# AD_inputs.net
KiCad netlist of a schematic drawn in EAGLE
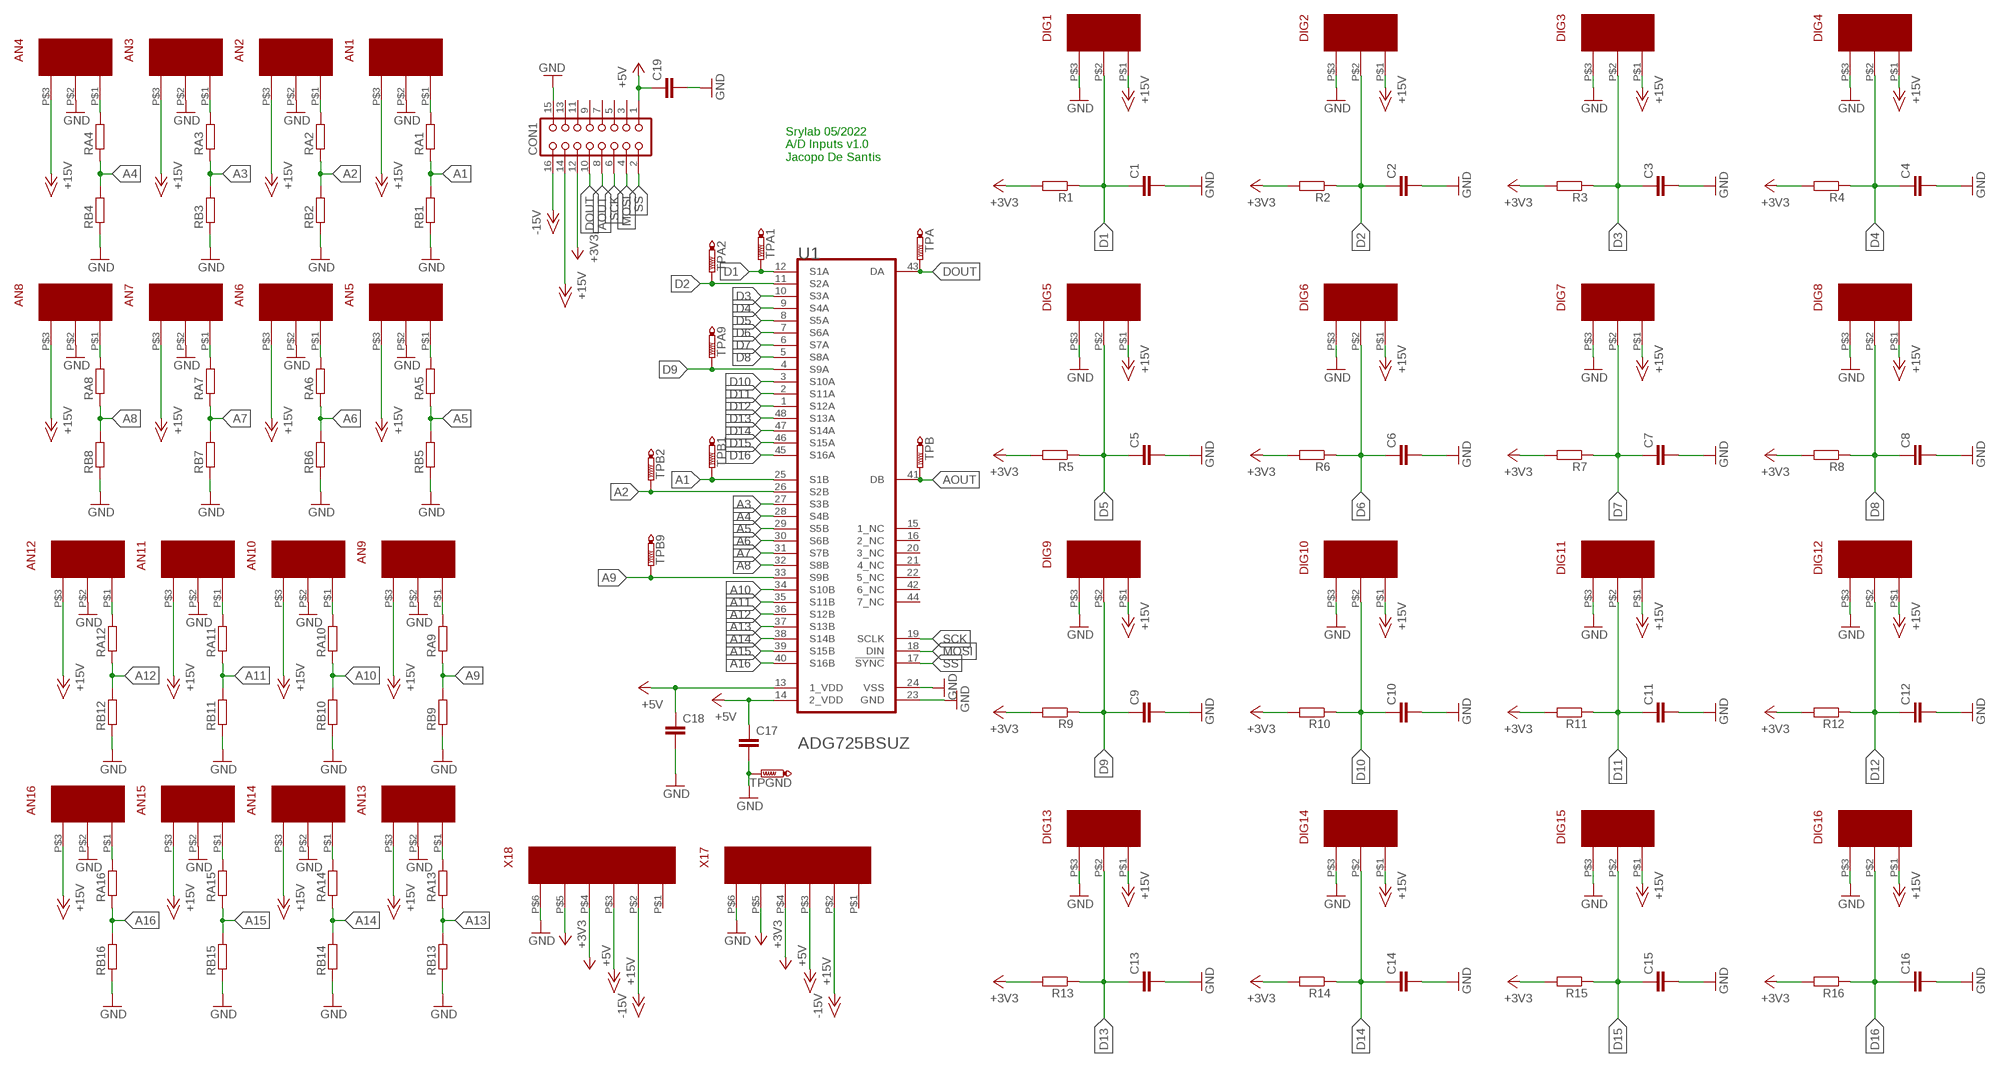
[diagram p0: schematic, sheet 1]

(export (version "E")
  (design (tool "Eeschema 10.0.6"))
  (components
    (comp (ref "AN1")
      (value "3PIN_CON")
      (footprint "eagle-import:3PIN_CON")
      (libsource (lib "eagle-import") (part "3PIN_CON"))
    )
    (comp (ref "AN2")
      (value "3PIN_CON")
      (footprint "eagle-import:3PIN_CON")
      (libsource (lib "eagle-import") (part "3PIN_CON"))
    )
    (comp (ref "AN3")
      (value "3PIN_CON")
      (footprint "eagle-import:3PIN_CON")
      (libsource (lib "eagle-import") (part "3PIN_CON"))
    )
    (comp (ref "AN4")
      (value "3PIN_CON")
      (footprint "eagle-import:3PIN_CON")
      (libsource (lib "eagle-import") (part "3PIN_CON"))
    )
    (comp (ref "AN5")
      (value "3PIN_CON")
      (footprint "eagle-import:3PIN_CON")
      (libsource (lib "eagle-import") (part "3PIN_CON"))
    )
    (comp (ref "AN6")
      (value "3PIN_CON")
      (footprint "eagle-import:3PIN_CON")
      (libsource (lib "eagle-import") (part "3PIN_CON"))
    )
    (comp (ref "AN7")
      (value "3PIN_CON")
      (footprint "eagle-import:3PIN_CON")
      (libsource (lib "eagle-import") (part "3PIN_CON"))
    )
    (comp (ref "AN8")
      (value "3PIN_CON")
      (footprint "eagle-import:3PIN_CON")
      (libsource (lib "eagle-import") (part "3PIN_CON"))
    )
    (comp (ref "AN9")
      (value "3PIN_CON")
      (footprint "eagle-import:3PIN_CON")
      (libsource (lib "eagle-import") (part "3PIN_CON"))
    )
    (comp (ref "AN10")
      (value "3PIN_CON")
      (footprint "eagle-import:3PIN_CON")
      (libsource (lib "eagle-import") (part "3PIN_CON"))
    )
    (comp (ref "AN11")
      (value "3PIN_CON")
      (footprint "eagle-import:3PIN_CON")
      (libsource (lib "eagle-import") (part "3PIN_CON"))
    )
    (comp (ref "AN12")
      (value "3PIN_CON")
      (footprint "eagle-import:3PIN_CON")
      (libsource (lib "eagle-import") (part "3PIN_CON"))
    )
    (comp (ref "AN13")
      (value "3PIN_CON")
      (footprint "eagle-import:3PIN_CON")
      (libsource (lib "eagle-import") (part "3PIN_CON"))
    )
    (comp (ref "AN14")
      (value "3PIN_CON")
      (footprint "eagle-import:3PIN_CON")
      (libsource (lib "eagle-import") (part "3PIN_CON"))
    )
    (comp (ref "AN15")
      (value "3PIN_CON")
      (footprint "eagle-import:3PIN_CON")
      (libsource (lib "eagle-import") (part "3PIN_CON"))
    )
    (comp (ref "AN16")
      (value "3PIN_CON")
      (footprint "eagle-import:3PIN_CON")
      (libsource (lib "eagle-import") (part "3PIN_CON"))
    )
    (comp (ref "C1")
      (value "C-EU_SMD0805")
      (footprint "eagle-import:C0805")
      (libsource (lib "eagle-import") (part "C-EU_SMD0805"))
    )
    (comp (ref "C2")
      (value "C-EU_SMD0805")
      (footprint "eagle-import:C0805")
      (libsource (lib "eagle-import") (part "C-EU_SMD0805"))
    )
    (comp (ref "C3")
      (value "C-EU_SMD0805")
      (footprint "eagle-import:C0805")
      (libsource (lib "eagle-import") (part "C-EU_SMD0805"))
    )
    (comp (ref "C4")
      (value "C-EU_SMD0805")
      (footprint "eagle-import:C0805")
      (libsource (lib "eagle-import") (part "C-EU_SMD0805"))
    )
    (comp (ref "C5")
      (value "C-EU_SMD0805")
      (footprint "eagle-import:C0805")
      (libsource (lib "eagle-import") (part "C-EU_SMD0805"))
    )
    (comp (ref "C6")
      (value "C-EU_SMD0805")
      (footprint "eagle-import:C0805")
      (libsource (lib "eagle-import") (part "C-EU_SMD0805"))
    )
    (comp (ref "C7")
      (value "C-EU_SMD0805")
      (footprint "eagle-import:C0805")
      (libsource (lib "eagle-import") (part "C-EU_SMD0805"))
    )
    (comp (ref "C8")
      (value "C-EU_SMD0805")
      (footprint "eagle-import:C0805")
      (libsource (lib "eagle-import") (part "C-EU_SMD0805"))
    )
    (comp (ref "C9")
      (value "C-EU_SMD0805")
      (footprint "eagle-import:C0805")
      (libsource (lib "eagle-import") (part "C-EU_SMD0805"))
    )
    (comp (ref "C10")
      (value "C-EU_SMD0805")
      (footprint "eagle-import:C0805")
      (libsource (lib "eagle-import") (part "C-EU_SMD0805"))
    )
    (comp (ref "C11")
      (value "C-EU_SMD0805")
      (footprint "eagle-import:C0805")
      (libsource (lib "eagle-import") (part "C-EU_SMD0805"))
    )
    (comp (ref "C12")
      (value "C-EU_SMD0805")
      (footprint "eagle-import:C0805")
      (libsource (lib "eagle-import") (part "C-EU_SMD0805"))
    )
    (comp (ref "C13")
      (value "C-EU_SMD0805")
      (footprint "eagle-import:C0805")
      (libsource (lib "eagle-import") (part "C-EU_SMD0805"))
    )
    (comp (ref "C14")
      (value "C-EU_SMD0805")
      (footprint "eagle-import:C0805")
      (libsource (lib "eagle-import") (part "C-EU_SMD0805"))
    )
    (comp (ref "C15")
      (value "C-EU_SMD0805")
      (footprint "eagle-import:C0805")
      (libsource (lib "eagle-import") (part "C-EU_SMD0805"))
    )
    (comp (ref "C16")
      (value "C-EU_SMD0805")
      (footprint "eagle-import:C0805")
      (libsource (lib "eagle-import") (part "C-EU_SMD0805"))
    )
    (comp (ref "C17")
      (value "C-EU_SMDC1206H/D")
      (footprint "eagle-import:C1206H_D")
      (libsource (lib "eagle-import") (part "C-EU_SMDC1206H/D"))
    )
    (comp (ref "C18")
      (value "C-EU_SMDC1206H/D")
      (footprint "eagle-import:C1206H_D")
      (libsource (lib "eagle-import") (part "C-EU_SMDC1206H/D"))
    )
    (comp (ref "C19")
      (value "C-EU_SMDC1206H/D")
      (footprint "eagle-import:C1206H_D")
      (libsource (lib "eagle-import") (part "C-EU_SMDC1206H/D"))
    )
    (comp (ref "CON1")
      (value "CON16L")
      (footprint "eagle-import:CON16L")
      (libsource (lib "eagle-import") (part "CON16L"))
    )
    (comp (ref "DIG1")
      (value "3PIN_CON")
      (footprint "eagle-import:3PIN_CON")
      (libsource (lib "eagle-import") (part "3PIN_CON"))
    )
    (comp (ref "DIG2")
      (value "3PIN_CON")
      (footprint "eagle-import:3PIN_CON")
      (libsource (lib "eagle-import") (part "3PIN_CON"))
    )
    (comp (ref "DIG3")
      (value "3PIN_CON")
      (footprint "eagle-import:3PIN_CON")
      (libsource (lib "eagle-import") (part "3PIN_CON"))
    )
    (comp (ref "DIG4")
      (value "3PIN_CON")
      (footprint "eagle-import:3PIN_CON")
      (libsource (lib "eagle-import") (part "3PIN_CON"))
    )
    (comp (ref "DIG5")
      (value "3PIN_CON")
      (footprint "eagle-import:3PIN_CON")
      (libsource (lib "eagle-import") (part "3PIN_CON"))
    )
    (comp (ref "DIG6")
      (value "3PIN_CON")
      (footprint "eagle-import:3PIN_CON")
      (libsource (lib "eagle-import") (part "3PIN_CON"))
    )
    (comp (ref "DIG7")
      (value "3PIN_CON")
      (footprint "eagle-import:3PIN_CON")
      (libsource (lib "eagle-import") (part "3PIN_CON"))
    )
    (comp (ref "DIG8")
      (value "3PIN_CON")
      (footprint "eagle-import:3PIN_CON")
      (libsource (lib "eagle-import") (part "3PIN_CON"))
    )
    (comp (ref "DIG9")
      (value "3PIN_CON")
      (footprint "eagle-import:3PIN_CON")
      (libsource (lib "eagle-import") (part "3PIN_CON"))
    )
    (comp (ref "DIG10")
      (value "3PIN_CON")
      (footprint "eagle-import:3PIN_CON")
      (libsource (lib "eagle-import") (part "3PIN_CON"))
    )
    (comp (ref "DIG11")
      (value "3PIN_CON")
      (footprint "eagle-import:3PIN_CON")
      (libsource (lib "eagle-import") (part "3PIN_CON"))
    )
    (comp (ref "DIG12")
      (value "3PIN_CON")
      (footprint "eagle-import:3PIN_CON")
      (libsource (lib "eagle-import") (part "3PIN_CON"))
    )
    (comp (ref "DIG13")
      (value "3PIN_CON")
      (footprint "eagle-import:3PIN_CON")
      (libsource (lib "eagle-import") (part "3PIN_CON"))
    )
    (comp (ref "DIG14")
      (value "3PIN_CON")
      (footprint "eagle-import:3PIN_CON")
      (libsource (lib "eagle-import") (part "3PIN_CON"))
    )
    (comp (ref "DIG15")
      (value "3PIN_CON")
      (footprint "eagle-import:3PIN_CON")
      (libsource (lib "eagle-import") (part "3PIN_CON"))
    )
    (comp (ref "DIG16")
      (value "3PIN_CON")
      (footprint "eagle-import:3PIN_CON")
      (libsource (lib "eagle-import") (part "3PIN_CON"))
    )
    (comp (ref "R1")
      (value "R-EU_SMD0805H")
      (footprint "eagle-import:R0805H")
      (libsource (lib "eagle-import") (part "R-EU_SMD0805H"))
    )
    (comp (ref "R2")
      (value "R-EU_SMD0805H")
      (footprint "eagle-import:R0805H")
      (libsource (lib "eagle-import") (part "R-EU_SMD0805H"))
    )
    (comp (ref "R3")
      (value "R-EU_SMD0805H")
      (footprint "eagle-import:R0805H")
      (libsource (lib "eagle-import") (part "R-EU_SMD0805H"))
    )
    (comp (ref "R4")
      (value "R-EU_SMD0805H")
      (footprint "eagle-import:R0805H")
      (libsource (lib "eagle-import") (part "R-EU_SMD0805H"))
    )
    (comp (ref "R5")
      (value "R-EU_SMD0805H")
      (footprint "eagle-import:R0805H")
      (libsource (lib "eagle-import") (part "R-EU_SMD0805H"))
    )
    (comp (ref "R6")
      (value "R-EU_SMD0805H")
      (footprint "eagle-import:R0805H")
      (libsource (lib "eagle-import") (part "R-EU_SMD0805H"))
    )
    (comp (ref "R7")
      (value "R-EU_SMD0805H")
      (footprint "eagle-import:R0805H")
      (libsource (lib "eagle-import") (part "R-EU_SMD0805H"))
    )
    (comp (ref "R8")
      (value "R-EU_SMD0805H")
      (footprint "eagle-import:R0805H")
      (libsource (lib "eagle-import") (part "R-EU_SMD0805H"))
    )
    (comp (ref "R9")
      (value "R-EU_SMD0805H")
      (footprint "eagle-import:R0805H")
      (libsource (lib "eagle-import") (part "R-EU_SMD0805H"))
    )
    (comp (ref "R10")
      (value "R-EU_SMD0805H")
      (footprint "eagle-import:R0805H")
      (libsource (lib "eagle-import") (part "R-EU_SMD0805H"))
    )
    (comp (ref "R11")
      (value "R-EU_SMD0805H")
      (footprint "eagle-import:R0805H")
      (libsource (lib "eagle-import") (part "R-EU_SMD0805H"))
    )
    (comp (ref "R12")
      (value "R-EU_SMD0805H")
      (footprint "eagle-import:R0805H")
      (libsource (lib "eagle-import") (part "R-EU_SMD0805H"))
    )
    (comp (ref "R13")
      (value "R-EU_SMD0805H")
      (footprint "eagle-import:R0805H")
      (libsource (lib "eagle-import") (part "R-EU_SMD0805H"))
    )
    (comp (ref "R14")
      (value "R-EU_SMD0805H")
      (footprint "eagle-import:R0805H")
      (libsource (lib "eagle-import") (part "R-EU_SMD0805H"))
    )
    (comp (ref "R15")
      (value "R-EU_SMD0805H")
      (footprint "eagle-import:R0805H")
      (libsource (lib "eagle-import") (part "R-EU_SMD0805H"))
    )
    (comp (ref "R16")
      (value "R-EU_SMD0805H")
      (footprint "eagle-import:R0805H")
      (libsource (lib "eagle-import") (part "R-EU_SMD0805H"))
    )
    (comp (ref "RA1")
      (value "R-EU_SMD0805H")
      (footprint "eagle-import:R0805H")
      (libsource (lib "eagle-import") (part "R-EU_SMD0805H"))
    )
    (comp (ref "RA2")
      (value "R-EU_SMD0805H")
      (footprint "eagle-import:R0805H")
      (libsource (lib "eagle-import") (part "R-EU_SMD0805H"))
    )
    (comp (ref "RA3")
      (value "R-EU_SMD0805H")
      (footprint "eagle-import:R0805H")
      (libsource (lib "eagle-import") (part "R-EU_SMD0805H"))
    )
    (comp (ref "RA4")
      (value "R-EU_SMD0805H")
      (footprint "eagle-import:R0805H")
      (libsource (lib "eagle-import") (part "R-EU_SMD0805H"))
    )
    (comp (ref "RA5")
      (value "R-EU_SMD0805H")
      (footprint "eagle-import:R0805H")
      (libsource (lib "eagle-import") (part "R-EU_SMD0805H"))
    )
    (comp (ref "RA6")
      (value "R-EU_SMD0805H")
      (footprint "eagle-import:R0805H")
      (libsource (lib "eagle-import") (part "R-EU_SMD0805H"))
    )
    (comp (ref "RA7")
      (value "R-EU_SMD0805H")
      (footprint "eagle-import:R0805H")
      (libsource (lib "eagle-import") (part "R-EU_SMD0805H"))
    )
    (comp (ref "RA8")
      (value "R-EU_SMD0805H")
      (footprint "eagle-import:R0805H")
      (libsource (lib "eagle-import") (part "R-EU_SMD0805H"))
    )
    (comp (ref "RA9")
      (value "R-EU_SMD0805H")
      (footprint "eagle-import:R0805H")
      (libsource (lib "eagle-import") (part "R-EU_SMD0805H"))
    )
    (comp (ref "RA10")
      (value "R-EU_SMD0805H")
      (footprint "eagle-import:R0805H")
      (libsource (lib "eagle-import") (part "R-EU_SMD0805H"))
    )
    (comp (ref "RA11")
      (value "R-EU_SMD0805H")
      (footprint "eagle-import:R0805H")
      (libsource (lib "eagle-import") (part "R-EU_SMD0805H"))
    )
    (comp (ref "RA12")
      (value "R-EU_SMD0805H")
      (footprint "eagle-import:R0805H")
      (libsource (lib "eagle-import") (part "R-EU_SMD0805H"))
    )
    (comp (ref "RA13")
      (value "R-EU_SMD0805H")
      (footprint "eagle-import:R0805H")
      (libsource (lib "eagle-import") (part "R-EU_SMD0805H"))
    )
    (comp (ref "RA14")
      (value "R-EU_SMD0805H")
      (footprint "eagle-import:R0805H")
      (libsource (lib "eagle-import") (part "R-EU_SMD0805H"))
    )
    (comp (ref "RA15")
      (value "R-EU_SMD0805H")
      (footprint "eagle-import:R0805H")
      (libsource (lib "eagle-import") (part "R-EU_SMD0805H"))
    )
    (comp (ref "RA16")
      (value "R-EU_SMD0805H")
      (footprint "eagle-import:R0805H")
      (libsource (lib "eagle-import") (part "R-EU_SMD0805H"))
    )
    (comp (ref "RB1")
      (value "R-EU_SMD0805H")
      (footprint "eagle-import:R0805H")
      (libsource (lib "eagle-import") (part "R-EU_SMD0805H"))
    )
    (comp (ref "RB2")
      (value "R-EU_SMD0805H")
      (footprint "eagle-import:R0805H")
      (libsource (lib "eagle-import") (part "R-EU_SMD0805H"))
    )
    (comp (ref "RB3")
      (value "R-EU_SMD0805H")
      (footprint "eagle-import:R0805H")
      (libsource (lib "eagle-import") (part "R-EU_SMD0805H"))
    )
    (comp (ref "RB4")
      (value "R-EU_SMD0805H")
      (footprint "eagle-import:R0805H")
      (libsource (lib "eagle-import") (part "R-EU_SMD0805H"))
    )
    (comp (ref "RB5")
      (value "R-EU_SMD0805H")
      (footprint "eagle-import:R0805H")
      (libsource (lib "eagle-import") (part "R-EU_SMD0805H"))
    )
    (comp (ref "RB6")
      (value "R-EU_SMD0805H")
      (footprint "eagle-import:R0805H")
      (libsource (lib "eagle-import") (part "R-EU_SMD0805H"))
    )
    (comp (ref "RB7")
      (value "R-EU_SMD0805H")
      (footprint "eagle-import:R0805H")
      (libsource (lib "eagle-import") (part "R-EU_SMD0805H"))
    )
    (comp (ref "RB8")
      (value "R-EU_SMD0805H")
      (footprint "eagle-import:R0805H")
      (libsource (lib "eagle-import") (part "R-EU_SMD0805H"))
    )
    (comp (ref "RB9")
      (value "R-EU_SMD0805H")
      (footprint "eagle-import:R0805H")
      (libsource (lib "eagle-import") (part "R-EU_SMD0805H"))
    )
    (comp (ref "RB10")
      (value "R-EU_SMD0805H")
      (footprint "eagle-import:R0805H")
      (libsource (lib "eagle-import") (part "R-EU_SMD0805H"))
    )
    (comp (ref "RB11")
      (value "R-EU_SMD0805H")
      (footprint "eagle-import:R0805H")
      (libsource (lib "eagle-import") (part "R-EU_SMD0805H"))
    )
    (comp (ref "RB12")
      (value "R-EU_SMD0805H")
      (footprint "eagle-import:R0805H")
      (libsource (lib "eagle-import") (part "R-EU_SMD0805H"))
    )
    (comp (ref "RB13")
      (value "R-EU_SMD0805H")
      (footprint "eagle-import:R0805H")
      (libsource (lib "eagle-import") (part "R-EU_SMD0805H"))
    )
    (comp (ref "RB14")
      (value "R-EU_SMD0805H")
      (footprint "eagle-import:R0805H")
      (libsource (lib "eagle-import") (part "R-EU_SMD0805H"))
    )
    (comp (ref "RB15")
      (value "R-EU_SMD0805H")
      (footprint "eagle-import:R0805H")
      (libsource (lib "eagle-import") (part "R-EU_SMD0805H"))
    )
    (comp (ref "RB16")
      (value "R-EU_SMD0805H")
      (footprint "eagle-import:R0805H")
      (libsource (lib "eagle-import") (part "R-EU_SMD0805H"))
    )
    (comp (ref "TPA")
      (value "PTR1TP20R")
      (footprint "eagle-import:TP20R")
      (libsource (lib "eagle-import") (part "PTR1TP20R"))
    )
    (comp (ref "TPA1")
      (value "PTR1TP20R")
      (footprint "eagle-import:TP20R")
      (libsource (lib "eagle-import") (part "PTR1TP20R"))
    )
    (comp (ref "TPA2")
      (value "PTR1TP20R")
      (footprint "eagle-import:TP20R")
      (libsource (lib "eagle-import") (part "PTR1TP20R"))
    )
    (comp (ref "TPA9")
      (value "PTR1TP20R")
      (footprint "eagle-import:TP20R")
      (libsource (lib "eagle-import") (part "PTR1TP20R"))
    )
    (comp (ref "TPB")
      (value "PTR1TP20R")
      (footprint "eagle-import:TP20R")
      (libsource (lib "eagle-import") (part "PTR1TP20R"))
    )
    (comp (ref "TPB1")
      (value "PTR1TP20R")
      (footprint "eagle-import:TP20R")
      (libsource (lib "eagle-import") (part "PTR1TP20R"))
    )
    (comp (ref "TPB2")
      (value "PTR1TP20R")
      (footprint "eagle-import:TP20R")
      (libsource (lib "eagle-import") (part "PTR1TP20R"))
    )
    (comp (ref "TPB9")
      (value "PTR1TP20R")
      (footprint "eagle-import:TP20R")
      (libsource (lib "eagle-import") (part "PTR1TP20R"))
    )
    (comp (ref "TPGND")
      (value "PTR1TP20R")
      (footprint "eagle-import:TP20R")
      (libsource (lib "eagle-import") (part "PTR1TP20R"))
    )
    (comp (ref "U1")
      (value "ANALOG_DEVICES_ADG725BSUZANALOG_DEVICES_ADG725BSUZ_0_2")
      (footprint "eagle-import:ANALOG_DEVICES_ADG725BSUZ_2")
      (fields (field (name "MF") "Analog Devices") (field (name "MPN") "ADG725BSUZ"))
      (libsource (lib "eagle-import") (part "ANALOG_DEVICES_ADG725BSUZANALOG_DEVICES_ADG725BSUZ_0_2"))
    )
    (comp (ref "X17")
      (value "6PIN_CON")
      (footprint "eagle-import:6PIN_CON")
      (libsource (lib "eagle-import") (part "6PIN_CON"))
    )
    (comp (ref "X18")
      (value "6PIN_CON")
      (footprint "eagle-import:6PIN_CON")
      (libsource (lib "eagle-import") (part "6PIN_CON"))
    )
  )
  (nets
    (net (code "1") (name "+3V3") (class "Default")
      (node (ref "CON1") (pin "12") (pinfunction "12_12") (pintype "passive"))
      (node (ref "R1") (pin "2") (pinfunction "2_2") (pintype "passive"))
      (node (ref "R10") (pin "2") (pinfunction "2_2") (pintype "passive"))
      (node (ref "R11") (pin "2") (pinfunction "2_2") (pintype "passive"))
      (node (ref "R12") (pin "2") (pinfunction "2_2") (pintype "passive"))
      (node (ref "R13") (pin "2") (pinfunction "2_2") (pintype "passive"))
      (node (ref "R14") (pin "2") (pinfunction "2_2") (pintype "passive"))
      (node (ref "R15") (pin "2") (pinfunction "2_2") (pintype "passive"))
      (node (ref "R16") (pin "2") (pinfunction "2_2") (pintype "passive"))
      (node (ref "R2") (pin "2") (pinfunction "2_2") (pintype "passive"))
      (node (ref "R3") (pin "2") (pinfunction "2_2") (pintype "passive"))
      (node (ref "R4") (pin "2") (pinfunction "2_2") (pintype "passive"))
      (node (ref "R5") (pin "2") (pinfunction "2_2") (pintype "passive"))
      (node (ref "R6") (pin "2") (pinfunction "2_2") (pintype "passive"))
      (node (ref "R7") (pin "2") (pinfunction "2_2") (pintype "passive"))
      (node (ref "R8") (pin "2") (pinfunction "2_2") (pintype "passive"))
      (node (ref "R9") (pin "2") (pinfunction "2_2") (pintype "passive"))
      (node (ref "X17") (pin "P$5") (pinfunction "P$5_P$5") (pintype "bidirectional"))
      (node (ref "X18") (pin "P$5") (pinfunction "P$5_P$5") (pintype "bidirectional"))
    )
    (net (code "2") (name "+5V") (class "Default")
      (node (ref "C17") (pin "1") (pinfunction "1_1") (pintype "passive"))
      (node (ref "C18") (pin "1") (pinfunction "1_1") (pintype "passive"))
      (node (ref "C19") (pin "1") (pinfunction "1_1") (pintype "passive"))
      (node (ref "CON1") (pin "1") (pinfunction "1_1") (pintype "passive"))
      (node (ref "U1") (pin "13") (pinfunction "1_VDD_13") (pintype "power_in"))
      (node (ref "U1") (pin "14") (pinfunction "2_VDD_14") (pintype "power_in"))
      (node (ref "X17") (pin "P$4") (pinfunction "P$4_P$4") (pintype "bidirectional"))
      (node (ref "X18") (pin "P$4") (pinfunction "P$4_P$4") (pintype "bidirectional"))
    )
    (net (code "3") (name "+15V") (class "Default")
      (node (ref "AN1") (pin "P$3") (pinfunction "P$3_P$3") (pintype "bidirectional"))
      (node (ref "AN10") (pin "P$3") (pinfunction "P$3_P$3") (pintype "bidirectional"))
      (node (ref "AN11") (pin "P$3") (pinfunction "P$3_P$3") (pintype "bidirectional"))
      (node (ref "AN12") (pin "P$3") (pinfunction "P$3_P$3") (pintype "bidirectional"))
      (node (ref "AN13") (pin "P$3") (pinfunction "P$3_P$3") (pintype "bidirectional"))
      (node (ref "AN14") (pin "P$3") (pinfunction "P$3_P$3") (pintype "bidirectional"))
      (node (ref "AN15") (pin "P$3") (pinfunction "P$3_P$3") (pintype "bidirectional"))
      (node (ref "AN16") (pin "P$3") (pinfunction "P$3_P$3") (pintype "bidirectional"))
      (node (ref "AN2") (pin "P$3") (pinfunction "P$3_P$3") (pintype "bidirectional"))
      (node (ref "AN3") (pin "P$3") (pinfunction "P$3_P$3") (pintype "bidirectional"))
      (node (ref "AN4") (pin "P$3") (pinfunction "P$3_P$3") (pintype "bidirectional"))
      (node (ref "AN5") (pin "P$3") (pinfunction "P$3_P$3") (pintype "bidirectional"))
      (node (ref "AN6") (pin "P$3") (pinfunction "P$3_P$3") (pintype "bidirectional"))
      (node (ref "AN7") (pin "P$3") (pinfunction "P$3_P$3") (pintype "bidirectional"))
      (node (ref "AN8") (pin "P$3") (pinfunction "P$3_P$3") (pintype "bidirectional"))
      (node (ref "AN9") (pin "P$3") (pinfunction "P$3_P$3") (pintype "bidirectional"))
      (node (ref "CON1") (pin "14") (pinfunction "14_14") (pintype "passive"))
      (node (ref "DIG1") (pin "P$1") (pinfunction "P$1_P$1") (pintype "bidirectional"))
      (node (ref "DIG10") (pin "P$1") (pinfunction "P$1_P$1") (pintype "bidirectional"))
      (node (ref "DIG11") (pin "P$1") (pinfunction "P$1_P$1") (pintype "bidirectional"))
      (node (ref "DIG12") (pin "P$1") (pinfunction "P$1_P$1") (pintype "bidirectional"))
      (node (ref "DIG13") (pin "P$1") (pinfunction "P$1_P$1") (pintype "bidirectional"))
      (node (ref "DIG14") (pin "P$1") (pinfunction "P$1_P$1") (pintype "bidirectional"))
      (node (ref "DIG15") (pin "P$1") (pinfunction "P$1_P$1") (pintype "bidirectional"))
      (node (ref "DIG16") (pin "P$1") (pinfunction "P$1_P$1") (pintype "bidirectional"))
      (node (ref "DIG2") (pin "P$1") (pinfunction "P$1_P$1") (pintype "bidirectional"))
      (node (ref "DIG3") (pin "P$1") (pinfunction "P$1_P$1") (pintype "bidirectional"))
      (node (ref "DIG4") (pin "P$1") (pinfunction "P$1_P$1") (pintype "bidirectional"))
      (node (ref "DIG5") (pin "P$1") (pinfunction "P$1_P$1") (pintype "bidirectional"))
      (node (ref "DIG6") (pin "P$1") (pinfunction "P$1_P$1") (pintype "bidirectional"))
      (node (ref "DIG7") (pin "P$1") (pinfunction "P$1_P$1") (pintype "bidirectional"))
      (node (ref "DIG8") (pin "P$1") (pinfunction "P$1_P$1") (pintype "bidirectional"))
      (node (ref "DIG9") (pin "P$1") (pinfunction "P$1_P$1") (pintype "bidirectional"))
      (node (ref "X17") (pin "P$3") (pinfunction "P$3_P$3") (pintype "bidirectional"))
      (node (ref "X18") (pin "P$3") (pinfunction "P$3_P$3") (pintype "bidirectional"))
    )
    (net (code "4") (name "-15V") (class "Default")
      (node (ref "CON1") (pin "16") (pinfunction "16_16") (pintype "passive"))
      (node (ref "X17") (pin "P$2") (pinfunction "P$2_P$2") (pintype "bidirectional"))
      (node (ref "X18") (pin "P$2") (pinfunction "P$2_P$2") (pintype "bidirectional"))
    )
    (net (code "5") (name "A1") (class "Default")
      (node (ref "RA1") (pin "1") (pinfunction "1_1") (pintype "passive"))
      (node (ref "RB1") (pin "2") (pinfunction "2_2") (pintype "passive"))
      (node (ref "TPB1") (pin "TP") (pinfunction "TP_TP") (pintype "input"))
      (node (ref "U1") (pin "25") (pinfunction "S1B_25") (pintype "passive"))
    )
    (net (code "6") (name "A2") (class "Default")
      (node (ref "RA2") (pin "1") (pinfunction "1_1") (pintype "passive"))
      (node (ref "RB2") (pin "2") (pinfunction "2_2") (pintype "passive"))
      (node (ref "TPB2") (pin "TP") (pinfunction "TP_TP") (pintype "input"))
      (node (ref "U1") (pin "26") (pinfunction "S2B_26") (pintype "passive"))
    )
    (net (code "7") (name "A3") (class "Default")
      (node (ref "RA3") (pin "1") (pinfunction "1_1") (pintype "passive"))
      (node (ref "RB3") (pin "2") (pinfunction "2_2") (pintype "passive"))
      (node (ref "U1") (pin "27") (pinfunction "S3B_27") (pintype "passive"))
    )
    (net (code "8") (name "A4") (class "Default")
      (node (ref "RA4") (pin "1") (pinfunction "1_1") (pintype "passive"))
      (node (ref "RB4") (pin "2") (pinfunction "2_2") (pintype "passive"))
      (node (ref "U1") (pin "28") (pinfunction "S4B_28") (pintype "passive"))
    )
    (net (code "9") (name "A5") (class "Default")
      (node (ref "RA5") (pin "1") (pinfunction "1_1") (pintype "passive"))
      (node (ref "RB5") (pin "2") (pinfunction "2_2") (pintype "passive"))
      (node (ref "U1") (pin "29") (pinfunction "S5B_29") (pintype "passive"))
    )
    (net (code "10") (name "A6") (class "Default")
      (node (ref "RA6") (pin "1") (pinfunction "1_1") (pintype "passive"))
      (node (ref "RB6") (pin "2") (pinfunction "2_2") (pintype "passive"))
      (node (ref "U1") (pin "30") (pinfunction "S6B_30") (pintype "passive"))
    )
    (net (code "11") (name "A7") (class "Default")
      (node (ref "RA7") (pin "1") (pinfunction "1_1") (pintype "passive"))
      (node (ref "RB7") (pin "2") (pinfunction "2_2") (pintype "passive"))
      (node (ref "U1") (pin "31") (pinfunction "S7B_31") (pintype "passive"))
    )
    (net (code "12") (name "A8") (class "Default")
      (node (ref "RA8") (pin "1") (pinfunction "1_1") (pintype "passive"))
      (node (ref "RB8") (pin "2") (pinfunction "2_2") (pintype "passive"))
      (node (ref "U1") (pin "32") (pinfunction "S8B_32") (pintype "passive"))
    )
    (net (code "13") (name "A9") (class "Default")
      (node (ref "RA9") (pin "1") (pinfunction "1_1") (pintype "passive"))
      (node (ref "RB9") (pin "2") (pinfunction "2_2") (pintype "passive"))
      (node (ref "TPB9") (pin "TP") (pinfunction "TP_TP") (pintype "input"))
      (node (ref "U1") (pin "33") (pinfunction "S9B_33") (pintype "passive"))
    )
    (net (code "14") (name "A10") (class "Default")
      (node (ref "RA10") (pin "1") (pinfunction "1_1") (pintype "passive"))
      (node (ref "RB10") (pin "2") (pinfunction "2_2") (pintype "passive"))
      (node (ref "U1") (pin "34") (pinfunction "S10B_34") (pintype "passive"))
    )
    (net (code "15") (name "A11") (class "Default")
      (node (ref "RA11") (pin "1") (pinfunction "1_1") (pintype "passive"))
      (node (ref "RB11") (pin "2") (pinfunction "2_2") (pintype "passive"))
      (node (ref "U1") (pin "35") (pinfunction "S11B_35") (pintype "passive"))
    )
    (net (code "16") (name "A12") (class "Default")
      (node (ref "RA12") (pin "1") (pinfunction "1_1") (pintype "passive"))
      (node (ref "RB12") (pin "2") (pinfunction "2_2") (pintype "passive"))
      (node (ref "U1") (pin "36") (pinfunction "S12B_36") (pintype "passive"))
    )
    (net (code "17") (name "A13") (class "Default")
      (node (ref "RA13") (pin "1") (pinfunction "1_1") (pintype "passive"))
      (node (ref "RB13") (pin "2") (pinfunction "2_2") (pintype "passive"))
      (node (ref "U1") (pin "37") (pinfunction "S13B_37") (pintype "passive"))
    )
    (net (code "18") (name "A14") (class "Default")
      (node (ref "RA14") (pin "1") (pinfunction "1_1") (pintype "passive"))
      (node (ref "RB14") (pin "2") (pinfunction "2_2") (pintype "passive"))
      (node (ref "U1") (pin "38") (pinfunction "S14B_38") (pintype "passive"))
    )
    (net (code "19") (name "A15") (class "Default")
      (node (ref "RA15") (pin "1") (pinfunction "1_1") (pintype "passive"))
      (node (ref "RB15") (pin "2") (pinfunction "2_2") (pintype "passive"))
      (node (ref "U1") (pin "39") (pinfunction "S15B_39") (pintype "passive"))
    )
    (net (code "20") (name "A16") (class "Default")
      (node (ref "RA16") (pin "1") (pinfunction "1_1") (pintype "passive"))
      (node (ref "RB16") (pin "2") (pinfunction "2_2") (pintype "passive"))
      (node (ref "U1") (pin "40") (pinfunction "S16B_40") (pintype "passive"))
    )
    (net (code "21") (name "AOUT") (class "Default")
      (node (ref "CON1") (pin "8") (pinfunction "8_8") (pintype "passive"))
      (node (ref "TPB") (pin "TP") (pinfunction "TP_TP") (pintype "input"))
      (node (ref "U1") (pin "41") (pinfunction "DB_41") (pintype "passive"))
    )
    (net (code "22") (name "D1") (class "Default")
      (node (ref "C1") (pin "1") (pinfunction "1_1") (pintype "passive"))
      (node (ref "DIG1") (pin "P$2") (pinfunction "P$2_P$2") (pintype "bidirectional"))
      (node (ref "R1") (pin "1") (pinfunction "1_1") (pintype "passive"))
      (node (ref "TPA1") (pin "TP") (pinfunction "TP_TP") (pintype "input"))
      (node (ref "U1") (pin "12") (pinfunction "S1A_12") (pintype "passive"))
    )
    (net (code "23") (name "D2") (class "Default")
      (node (ref "C2") (pin "1") (pinfunction "1_1") (pintype "passive"))
      (node (ref "DIG2") (pin "P$2") (pinfunction "P$2_P$2") (pintype "bidirectional"))
      (node (ref "R2") (pin "1") (pinfunction "1_1") (pintype "passive"))
      (node (ref "TPA2") (pin "TP") (pinfunction "TP_TP") (pintype "input"))
      (node (ref "U1") (pin "11") (pinfunction "S2A_11") (pintype "passive"))
    )
    (net (code "24") (name "D3") (class "Default")
      (node (ref "C3") (pin "1") (pinfunction "1_1") (pintype "passive"))
      (node (ref "DIG3") (pin "P$2") (pinfunction "P$2_P$2") (pintype "bidirectional"))
      (node (ref "R3") (pin "1") (pinfunction "1_1") (pintype "passive"))
      (node (ref "U1") (pin "10") (pinfunction "S3A_10") (pintype "passive"))
    )
    (net (code "25") (name "D4") (class "Default")
      (node (ref "C4") (pin "1") (pinfunction "1_1") (pintype "passive"))
      (node (ref "DIG4") (pin "P$2") (pinfunction "P$2_P$2") (pintype "bidirectional"))
      (node (ref "R4") (pin "1") (pinfunction "1_1") (pintype "passive"))
      (node (ref "U1") (pin "9") (pinfunction "S4A_9") (pintype "passive"))
    )
    (net (code "26") (name "D5") (class "Default")
      (node (ref "C5") (pin "1") (pinfunction "1_1") (pintype "passive"))
      (node (ref "DIG5") (pin "P$2") (pinfunction "P$2_P$2") (pintype "bidirectional"))
      (node (ref "R5") (pin "1") (pinfunction "1_1") (pintype "passive"))
      (node (ref "U1") (pin "8") (pinfunction "S5A_8") (pintype "passive"))
    )
    (net (code "27") (name "D6") (class "Default")
      (node (ref "C6") (pin "1") (pinfunction "1_1") (pintype "passive"))
      (node (ref "DIG6") (pin "P$2") (pinfunction "P$2_P$2") (pintype "bidirectional"))
      (node (ref "R6") (pin "1") (pinfunction "1_1") (pintype "passive"))
      (node (ref "U1") (pin "7") (pinfunction "S6A_7") (pintype "passive"))
    )
    (net (code "28") (name "D7") (class "Default")
      (node (ref "C7") (pin "1") (pinfunction "1_1") (pintype "passive"))
      (node (ref "DIG7") (pin "P$2") (pinfunction "P$2_P$2") (pintype "bidirectional"))
      (node (ref "R7") (pin "1") (pinfunction "1_1") (pintype "passive"))
      (node (ref "U1") (pin "6") (pinfunction "S7A_6") (pintype "passive"))
    )
    (net (code "29") (name "D8") (class "Default")
      (node (ref "C8") (pin "1") (pinfunction "1_1") (pintype "passive"))
      (node (ref "DIG8") (pin "P$2") (pinfunction "P$2_P$2") (pintype "bidirectional"))
      (node (ref "R8") (pin "1") (pinfunction "1_1") (pintype "passive"))
      (node (ref "U1") (pin "5") (pinfunction "S8A_5") (pintype "passive"))
    )
    (net (code "30") (name "D9") (class "Default")
      (node (ref "C9") (pin "1") (pinfunction "1_1") (pintype "passive"))
      (node (ref "DIG9") (pin "P$2") (pinfunction "P$2_P$2") (pintype "bidirectional"))
      (node (ref "R9") (pin "1") (pinfunction "1_1") (pintype "passive"))
      (node (ref "TPA9") (pin "TP") (pinfunction "TP_TP") (pintype "input"))
      (node (ref "U1") (pin "4") (pinfunction "S9A_4") (pintype "passive"))
    )
    (net (code "31") (name "D10") (class "Default")
      (node (ref "C10") (pin "1") (pinfunction "1_1") (pintype "passive"))
      (node (ref "DIG10") (pin "P$2") (pinfunction "P$2_P$2") (pintype "bidirectional"))
      (node (ref "R10") (pin "1") (pinfunction "1_1") (pintype "passive"))
      (node (ref "U1") (pin "3") (pinfunction "S10A_3") (pintype "passive"))
    )
    (net (code "32") (name "D11") (class "Default")
      (node (ref "C11") (pin "1") (pinfunction "1_1") (pintype "passive"))
      (node (ref "DIG11") (pin "P$2") (pinfunction "P$2_P$2") (pintype "bidirectional"))
      (node (ref "R11") (pin "1") (pinfunction "1_1") (pintype "passive"))
      (node (ref "U1") (pin "2") (pinfunction "S11A_2") (pintype "passive"))
    )
    (net (code "33") (name "D12") (class "Default")
      (node (ref "C12") (pin "1") (pinfunction "1_1") (pintype "passive"))
      (node (ref "DIG12") (pin "P$2") (pinfunction "P$2_P$2") (pintype "bidirectional"))
      (node (ref "R12") (pin "1") (pinfunction "1_1") (pintype "passive"))
      (node (ref "U1") (pin "1") (pinfunction "S12A_1") (pintype "passive"))
    )
    (net (code "34") (name "D13") (class "Default")
      (node (ref "C13") (pin "1") (pinfunction "1_1") (pintype "passive"))
      (node (ref "DIG13") (pin "P$2") (pinfunction "P$2_P$2") (pintype "bidirectional"))
      (node (ref "R13") (pin "1") (pinfunction "1_1") (pintype "passive"))
      (node (ref "U1") (pin "48") (pinfunction "S13A_48") (pintype "passive"))
    )
    (net (code "35") (name "D14") (class "Default")
      (node (ref "C14") (pin "1") (pinfunction "1_1") (pintype "passive"))
      (node (ref "DIG14") (pin "P$2") (pinfunction "P$2_P$2") (pintype "bidirectional"))
      (node (ref "R14") (pin "1") (pinfunction "1_1") (pintype "passive"))
      (node (ref "U1") (pin "47") (pinfunction "S14A_47") (pintype "passive"))
    )
    (net (code "36") (name "D15") (class "Default")
      (node (ref "C15") (pin "1") (pinfunction "1_1") (pintype "passive"))
      (node (ref "DIG15") (pin "P$2") (pinfunction "P$2_P$2") (pintype "bidirectional"))
      (node (ref "R15") (pin "1") (pinfunction "1_1") (pintype "passive"))
      (node (ref "U1") (pin "46") (pinfunction "S15A_46") (pintype "passive"))
    )
    (net (code "37") (name "D16") (class "Default")
      (node (ref "C16") (pin "1") (pinfunction "1_1") (pintype "passive"))
      (node (ref "DIG16") (pin "P$2") (pinfunction "P$2_P$2") (pintype "bidirectional"))
      (node (ref "R16") (pin "1") (pinfunction "1_1") (pintype "passive"))
      (node (ref "U1") (pin "45") (pinfunction "S16A_45") (pintype "passive"))
    )
    (net (code "38") (name "DOUT") (class "Default")
      (node (ref "CON1") (pin "10") (pinfunction "10_10") (pintype "passive"))
      (node (ref "TPA") (pin "TP") (pinfunction "TP_TP") (pintype "input"))
      (node (ref "U1") (pin "43") (pinfunction "DA_43") (pintype "passive"))
    )
    (net (code "39") (name "GND") (class "Default")
      (node (ref "AN1") (pin "P$2") (pinfunction "P$2_P$2") (pintype "bidirectional"))
      (node (ref "AN10") (pin "P$2") (pinfunction "P$2_P$2") (pintype "bidirectional"))
      (node (ref "AN11") (pin "P$2") (pinfunction "P$2_P$2") (pintype "bidirectional"))
      (node (ref "AN12") (pin "P$2") (pinfunction "P$2_P$2") (pintype "bidirectional"))
      (node (ref "AN13") (pin "P$2") (pinfunction "P$2_P$2") (pintype "bidirectional"))
      (node (ref "AN14") (pin "P$2") (pinfunction "P$2_P$2") (pintype "bidirectional"))
      (node (ref "AN15") (pin "P$2") (pinfunction "P$2_P$2") (pintype "bidirectional"))
      (node (ref "AN16") (pin "P$2") (pinfunction "P$2_P$2") (pintype "bidirectional"))
      (node (ref "AN2") (pin "P$2") (pinfunction "P$2_P$2") (pintype "bidirectional"))
      (node (ref "AN3") (pin "P$2") (pinfunction "P$2_P$2") (pintype "bidirectional"))
      (node (ref "AN4") (pin "P$2") (pinfunction "P$2_P$2") (pintype "bidirectional"))
      (node (ref "AN5") (pin "P$2") (pinfunction "P$2_P$2") (pintype "bidirectional"))
      (node (ref "AN6") (pin "P$2") (pinfunction "P$2_P$2") (pintype "bidirectional"))
      (node (ref "AN7") (pin "P$2") (pinfunction "P$2_P$2") (pintype "bidirectional"))
      (node (ref "AN8") (pin "P$2") (pinfunction "P$2_P$2") (pintype "bidirectional"))
      (node (ref "AN9") (pin "P$2") (pinfunction "P$2_P$2") (pintype "bidirectional"))
      (node (ref "C1") (pin "2") (pinfunction "2_2") (pintype "passive"))
      (node (ref "C10") (pin "2") (pinfunction "2_2") (pintype "passive"))
      (node (ref "C11") (pin "2") (pinfunction "2_2") (pintype "passive"))
      (node (ref "C12") (pin "2") (pinfunction "2_2") (pintype "passive"))
      (node (ref "C13") (pin "2") (pinfunction "2_2") (pintype "passive"))
      (node (ref "C14") (pin "2") (pinfunction "2_2") (pintype "passive"))
      (node (ref "C15") (pin "2") (pinfunction "2_2") (pintype "passive"))
      (node (ref "C16") (pin "2") (pinfunction "2_2") (pintype "passive"))
      (node (ref "C17") (pin "2") (pinfunction "2_2") (pintype "passive"))
      (node (ref "C18") (pin "2") (pinfunction "2_2") (pintype "passive"))
      (node (ref "C19") (pin "2") (pinfunction "2_2") (pintype "passive"))
      (node (ref "C2") (pin "2") (pinfunction "2_2") (pintype "passive"))
      (node (ref "C3") (pin "2") (pinfunction "2_2") (pintype "passive"))
      (node (ref "C4") (pin "2") (pinfunction "2_2") (pintype "passive"))
      (node (ref "C5") (pin "2") (pinfunction "2_2") (pintype "passive"))
      (node (ref "C6") (pin "2") (pinfunction "2_2") (pintype "passive"))
      (node (ref "C7") (pin "2") (pinfunction "2_2") (pintype "passive"))
      (node (ref "C8") (pin "2") (pinfunction "2_2") (pintype "passive"))
      (node (ref "C9") (pin "2") (pinfunction "2_2") (pintype "passive"))
      (node (ref "CON1") (pin "15") (pinfunction "15_15") (pintype "passive"))
      (node (ref "DIG1") (pin "P$3") (pinfunction "P$3_P$3") (pintype "bidirectional"))
      (node (ref "DIG10") (pin "P$3") (pinfunction "P$3_P$3") (pintype "bidirectional"))
      (node (ref "DIG11") (pin "P$3") (pinfunction "P$3_P$3") (pintype "bidirectional"))
      (node (ref "DIG12") (pin "P$3") (pinfunction "P$3_P$3") (pintype "bidirectional"))
      (node (ref "DIG13") (pin "P$3") (pinfunction "P$3_P$3") (pintype "bidirectional"))
      (node (ref "DIG14") (pin "P$3") (pinfunction "P$3_P$3") (pintype "bidirectional"))
      (node (ref "DIG15") (pin "P$3") (pinfunction "P$3_P$3") (pintype "bidirectional"))
      (node (ref "DIG16") (pin "P$3") (pinfunction "P$3_P$3") (pintype "bidirectional"))
      (node (ref "DIG2") (pin "P$3") (pinfunction "P$3_P$3") (pintype "bidirectional"))
      (node (ref "DIG3") (pin "P$3") (pinfunction "P$3_P$3") (pintype "bidirectional"))
      (node (ref "DIG4") (pin "P$3") (pinfunction "P$3_P$3") (pintype "bidirectional"))
      (node (ref "DIG5") (pin "P$3") (pinfunction "P$3_P$3") (pintype "bidirectional"))
      (node (ref "DIG6") (pin "P$3") (pinfunction "P$3_P$3") (pintype "bidirectional"))
      (node (ref "DIG7") (pin "P$3") (pinfunction "P$3_P$3") (pintype "bidirectional"))
      (node (ref "DIG8") (pin "P$3") (pinfunction "P$3_P$3") (pintype "bidirectional"))
      (node (ref "DIG9") (pin "P$3") (pinfunction "P$3_P$3") (pintype "bidirectional"))
      (node (ref "RB1") (pin "1") (pinfunction "1_1") (pintype "passive"))
      (node (ref "RB10") (pin "1") (pinfunction "1_1") (pintype "passive"))
      (node (ref "RB11") (pin "1") (pinfunction "1_1") (pintype "passive"))
      (node (ref "RB12") (pin "1") (pinfunction "1_1") (pintype "passive"))
      (node (ref "RB13") (pin "1") (pinfunction "1_1") (pintype "passive"))
      (node (ref "RB14") (pin "1") (pinfunction "1_1") (pintype "passive"))
      (node (ref "RB15") (pin "1") (pinfunction "1_1") (pintype "passive"))
      (node (ref "RB16") (pin "1") (pinfunction "1_1") (pintype "passive"))
      (node (ref "RB2") (pin "1") (pinfunction "1_1") (pintype "passive"))
      (node (ref "RB3") (pin "1") (pinfunction "1_1") (pintype "passive"))
      (node (ref "RB4") (pin "1") (pinfunction "1_1") (pintype "passive"))
      (node (ref "RB5") (pin "1") (pinfunction "1_1") (pintype "passive"))
      (node (ref "RB6") (pin "1") (pinfunction "1_1") (pintype "passive"))
      (node (ref "RB7") (pin "1") (pinfunction "1_1") (pintype "passive"))
      (node (ref "RB8") (pin "1") (pinfunction "1_1") (pintype "passive"))
      (node (ref "RB9") (pin "1") (pinfunction "1_1") (pintype "passive"))
      (node (ref "TPGND") (pin "TP") (pinfunction "TP_TP") (pintype "input"))
      (node (ref "U1") (pin "23") (pinfunction "GND_23") (pintype "power_in"))
      (node (ref "U1") (pin "24") (pinfunction "VSS_24") (pintype "power_in"))
      (node (ref "X17") (pin "P$6") (pinfunction "P$6_P$6") (pintype "bidirectional"))
      (node (ref "X18") (pin "P$6") (pinfunction "P$6_P$6") (pintype "bidirectional"))
    )
    (net (code "40") (name "MOSI") (class "Default")
      (node (ref "CON1") (pin "4") (pinfunction "4_4") (pintype "passive"))
      (node (ref "U1") (pin "18") (pinfunction "DIN_18") (pintype "input"))
    )
    (net (code "41") (name "Net-(AN1-PadP$1)") (class "Default")
      (node (ref "AN1") (pin "P$1") (pinfunction "P$1_P$1") (pintype "bidirectional"))
      (node (ref "RA1") (pin "2") (pinfunction "2_2") (pintype "passive"))
    )
    (net (code "42") (name "Net-(AN2-PadP$1)") (class "Default")
      (node (ref "AN2") (pin "P$1") (pinfunction "P$1_P$1") (pintype "bidirectional"))
      (node (ref "RA2") (pin "2") (pinfunction "2_2") (pintype "passive"))
    )
    (net (code "43") (name "Net-(AN3-PadP$1)") (class "Default")
      (node (ref "AN3") (pin "P$1") (pinfunction "P$1_P$1") (pintype "bidirectional"))
      (node (ref "RA3") (pin "2") (pinfunction "2_2") (pintype "passive"))
    )
    (net (code "44") (name "Net-(AN4-PadP$1)") (class "Default")
      (node (ref "AN4") (pin "P$1") (pinfunction "P$1_P$1") (pintype "bidirectional"))
      (node (ref "RA4") (pin "2") (pinfunction "2_2") (pintype "passive"))
    )
    (net (code "45") (name "Net-(AN5-PadP$1)") (class "Default")
      (node (ref "AN5") (pin "P$1") (pinfunction "P$1_P$1") (pintype "bidirectional"))
      (node (ref "RA5") (pin "2") (pinfunction "2_2") (pintype "passive"))
    )
    (net (code "46") (name "Net-(AN6-PadP$1)") (class "Default")
      (node (ref "AN6") (pin "P$1") (pinfunction "P$1_P$1") (pintype "bidirectional"))
      (node (ref "RA6") (pin "2") (pinfunction "2_2") (pintype "passive"))
    )
    (net (code "47") (name "Net-(AN7-PadP$1)") (class "Default")
      (node (ref "AN7") (pin "P$1") (pinfunction "P$1_P$1") (pintype "bidirectional"))
      (node (ref "RA7") (pin "2") (pinfunction "2_2") (pintype "passive"))
    )
    (net (code "48") (name "Net-(AN8-PadP$1)") (class "Default")
      (node (ref "AN8") (pin "P$1") (pinfunction "P$1_P$1") (pintype "bidirectional"))
      (node (ref "RA8") (pin "2") (pinfunction "2_2") (pintype "passive"))
    )
    (net (code "49") (name "Net-(AN9-PadP$1)") (class "Default")
      (node (ref "AN9") (pin "P$1") (pinfunction "P$1_P$1") (pintype "bidirectional"))
      (node (ref "RA9") (pin "2") (pinfunction "2_2") (pintype "passive"))
    )
    (net (code "50") (name "Net-(AN10-PadP$1)") (class "Default")
      (node (ref "AN10") (pin "P$1") (pinfunction "P$1_P$1") (pintype "bidirectional"))
      (node (ref "RA10") (pin "2") (pinfunction "2_2") (pintype "passive"))
    )
    (net (code "51") (name "Net-(AN11-PadP$1)") (class "Default")
      (node (ref "AN11") (pin "P$1") (pinfunction "P$1_P$1") (pintype "bidirectional"))
      (node (ref "RA11") (pin "2") (pinfunction "2_2") (pintype "passive"))
    )
    (net (code "52") (name "Net-(AN12-PadP$1)") (class "Default")
      (node (ref "AN12") (pin "P$1") (pinfunction "P$1_P$1") (pintype "bidirectional"))
      (node (ref "RA12") (pin "2") (pinfunction "2_2") (pintype "passive"))
    )
    (net (code "53") (name "Net-(AN13-PadP$1)") (class "Default")
      (node (ref "AN13") (pin "P$1") (pinfunction "P$1_P$1") (pintype "bidirectional"))
      (node (ref "RA13") (pin "2") (pinfunction "2_2") (pintype "passive"))
    )
    (net (code "54") (name "Net-(AN14-PadP$1)") (class "Default")
      (node (ref "AN14") (pin "P$1") (pinfunction "P$1_P$1") (pintype "bidirectional"))
      (node (ref "RA14") (pin "2") (pinfunction "2_2") (pintype "passive"))
    )
    (net (code "55") (name "Net-(AN15-PadP$1)") (class "Default")
      (node (ref "AN15") (pin "P$1") (pinfunction "P$1_P$1") (pintype "bidirectional"))
      (node (ref "RA15") (pin "2") (pinfunction "2_2") (pintype "passive"))
    )
    (net (code "56") (name "Net-(AN16-PadP$1)") (class "Default")
      (node (ref "AN16") (pin "P$1") (pinfunction "P$1_P$1") (pintype "bidirectional"))
      (node (ref "RA16") (pin "2") (pinfunction "2_2") (pintype "passive"))
    )
    (net (code "57") (name "SCK") (class "Default")
      (node (ref "CON1") (pin "6") (pinfunction "6_6") (pintype "passive"))
      (node (ref "U1") (pin "19") (pinfunction "SCLK_19") (pintype "input"))
    )
    (net (code "58") (name "SS") (class "Default")
      (node (ref "CON1") (pin "2") (pinfunction "2_2") (pintype "passive"))
      (node (ref "U1") (pin "17") (pinfunction "~{SYNC}_17") (pintype "input"))
    )
    (net (code "59") (name "unconnected-(CON1-Pad3)") (class "Default")
      (node (ref "CON1") (pin "3") (pinfunction "3_3") (pintype "passive"))
    )
    (net (code "60") (name "unconnected-(CON1-Pad5)") (class "Default")
      (node (ref "CON1") (pin "5") (pinfunction "5_5") (pintype "passive"))
    )
    (net (code "61") (name "unconnected-(CON1-Pad7)") (class "Default")
      (node (ref "CON1") (pin "7") (pinfunction "7_7") (pintype "passive"))
    )
    (net (code "62") (name "unconnected-(CON1-Pad9)") (class "Default")
      (node (ref "CON1") (pin "9") (pinfunction "9_9") (pintype "passive"))
    )
    (net (code "63") (name "unconnected-(CON1-Pad11)") (class "Default")
      (node (ref "CON1") (pin "11") (pinfunction "11_11") (pintype "passive"))
    )
    (net (code "64") (name "unconnected-(CON1-Pad13)") (class "Default")
      (node (ref "CON1") (pin "13") (pinfunction "13_13") (pintype "passive"))
    )
    (net (code "65") (name "unconnected-(U1-1_NC-Pad15)") (class "Default")
      (node (ref "U1") (pin "15") (pinfunction "1_NC_15") (pintype "passive"))
    )
    (net (code "66") (name "unconnected-(U1-2_NC-Pad16)") (class "Default")
      (node (ref "U1") (pin "16") (pinfunction "2_NC_16") (pintype "passive"))
    )
    (net (code "67") (name "unconnected-(U1-3_NC-Pad20)") (class "Default")
      (node (ref "U1") (pin "20") (pinfunction "3_NC_20") (pintype "passive"))
    )
    (net (code "68") (name "unconnected-(U1-4_NC-Pad21)") (class "Default")
      (node (ref "U1") (pin "21") (pinfunction "4_NC_21") (pintype "passive"))
    )
    (net (code "69") (name "unconnected-(U1-5_NC-Pad22)") (class "Default")
      (node (ref "U1") (pin "22") (pinfunction "5_NC_22") (pintype "passive"))
    )
    (net (code "70") (name "unconnected-(U1-6_NC-Pad42)") (class "Default")
      (node (ref "U1") (pin "42") (pinfunction "6_NC_42") (pintype "passive"))
    )
    (net (code "71") (name "unconnected-(U1-7_NC-Pad44)") (class "Default")
      (node (ref "U1") (pin "44") (pinfunction "7_NC_44") (pintype "passive"))
    )
    (net (code "72") (name "unconnected-(X17-PadP$1)") (class "Default")
      (node (ref "X17") (pin "P$1") (pinfunction "P$1_P$1") (pintype "bidirectional"))
    )
    (net (code "73") (name "unconnected-(X18-PadP$1)") (class "Default")
      (node (ref "X18") (pin "P$1") (pinfunction "P$1_P$1") (pintype "bidirectional"))
    )
  )
)
